# cpu.net
KiCad netlist of a schematic drawn in Altium Designer
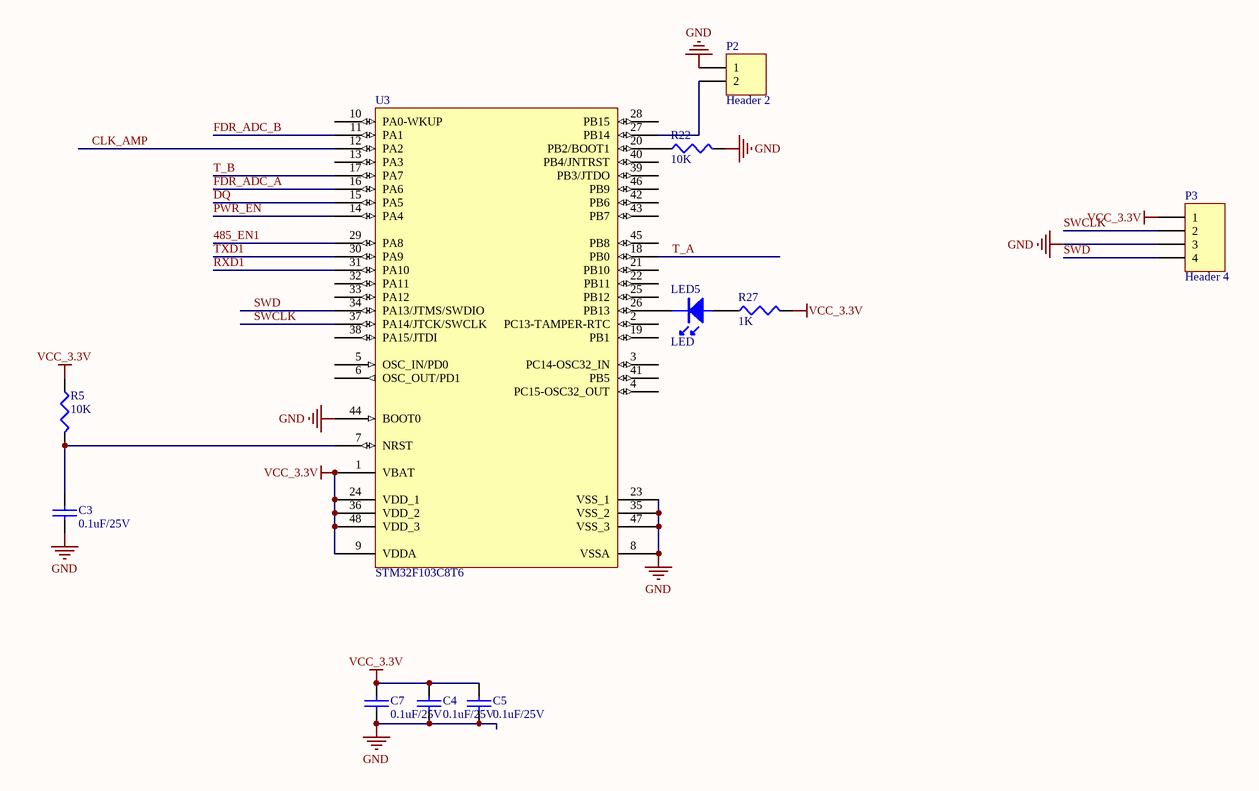
[diagram p0: cpu.SchDoc]

(export (version "E")
  (design (tool "Eeschema 10.0.6"))
  (components
    (comp (ref "C3")
      (value "0.1uF/25V")
      (footprint "0603C")
      (description "Capacitor")
      (libsource (lib "SM") (part "CAP"))
    )
    (comp (ref "C4")
      (value "0.1uF/25V")
      (footprint "0603C")
      (description "Capacitor")
      (libsource (lib "SM") (part "CAP"))
    )
    (comp (ref "C5")
      (value "0.1uF/25V")
      (footprint "0603C")
      (description "Capacitor")
      (libsource (lib "SM") (part "CAP"))
    )
    (comp (ref "C7")
      (value "0.1uF/25V")
      (footprint "0603C")
      (description "Capacitor")
      (libsource (lib "SM") (part "CAP"))
    )
    (comp (ref "LED5") (value "LED") (footprint "0603LED") (libsource (lib "我的元件库") (part "LED")))
    (comp (ref "P2")
      (value "Header 2")
      (footprint "HDR1X2")
      (description "Header, 2-Pin")
      (fields (field (name "PUBLISHER") "Altium Limited"))
      (libsource (lib "Miscellaneous Connectors") (part "Header 2"))
    )
    (comp (ref "P3")
      (value "Header 4")
      (footprint "HDR1X4")
      (description "Header, 4-Pin")
      (fields (field (name "PUBLISHER") "Altium Limited"))
      (libsource (lib "Miscellaneous Connectors") (part "Header 4"))
    )
    (comp (ref "R5")
      (value "10K")
      (footprint "0603R")
      (description "Resistor")
      (fields (field (name "PUBLISHER") "Altium Limited"))
      (libsource (lib "SM") (part "Res3"))
    )
    (comp (ref "R22")
      (value "10K")
      (footprint "0603R")
      (description "Resistor")
      (fields (field (name "PUBLISHER") "Altium Limited"))
      (libsource (lib "SM") (part "Res3"))
    )
    (comp (ref "R27")
      (value "1K")
      (footprint "0603R")
      (libsource (lib "ZWLIntegrated_Library") (part "RES1"))
    )
    (comp (ref "U3")
      (value "STM32F103C8T6")
      (footprint "TQFP-48")
      (description "STM32 ARM-based 32-bit MCU with 64 Kbytes Flash, 48-pin LQFP, Industrial Temperature")
      (fields (field (name "PUBLISHER") "Altium Limited"))
      (libsource (lib "ST Microcontroller 32-Bit STM32") (part "STM32F103C8T6"))
    )
  )
  (nets
    (net (code "1") (name "/485_EN1") (class "Default")
      (node (ref "U3") (pin "29") (pinfunction "PA8_29") (pintype "bidirectional"))
    )
    (net (code "2") (name "/CLK_AMP") (class "Default")
      (node (ref "U3") (pin "12") (pinfunction "PA2_12") (pintype "bidirectional"))
    )
    (net (code "3") (name "/DQ") (class "Default")
      (node (ref "U3") (pin "15") (pinfunction "PA5_15") (pintype "bidirectional"))
    )
    (net (code "4") (name "/FDR_ADC_A") (class "Default")
      (node (ref "U3") (pin "16") (pinfunction "PA6_16") (pintype "bidirectional"))
    )
    (net (code "5") (name "/FDR_ADC_B") (class "Default")
      (node (ref "U3") (pin "11") (pinfunction "PA1_11") (pintype "bidirectional"))
    )
    (net (code "6") (name "/PWR_EN") (class "Default")
      (node (ref "U3") (pin "14") (pinfunction "PA4_14") (pintype "bidirectional"))
    )
    (net (code "7") (name "/RXD1") (class "Default")
      (node (ref "U3") (pin "31") (pinfunction "PA10_31") (pintype "bidirectional"))
    )
    (net (code "8") (name "/SWCLK") (class "Default")
      (node (ref "P3") (pin "2") (pinfunction "2_2") (pintype "passive"))
      (node (ref "U3") (pin "37") (pinfunction "PA14/JTCK/SWCLK_37") (pintype "bidirectional"))
    )
    (net (code "9") (name "/SWD") (class "Default")
      (node (ref "P3") (pin "4") (pinfunction "4_4") (pintype "passive"))
      (node (ref "U3") (pin "34") (pinfunction "PA13/JTMS/SWDIO_34") (pintype "bidirectional"))
    )
    (net (code "10") (name "/TXD1") (class "Default")
      (node (ref "U3") (pin "30") (pinfunction "PA9_30") (pintype "bidirectional"))
    )
    (net (code "11") (name "/T_A") (class "Default")
      (node (ref "U3") (pin "18") (pinfunction "PB0_18") (pintype "bidirectional"))
    )
    (net (code "12") (name "/T_B") (class "Default")
      (node (ref "U3") (pin "17") (pinfunction "PA7_17") (pintype "bidirectional"))
    )
    (net (code "13") (name "GND") (class "Default")
      (node (ref "C3") (pin "1") (pinfunction "1_1") (pintype "passive"))
      (node (ref "C4") (pin "1") (pinfunction "1_1") (pintype "passive"))
      (node (ref "C5") (pin "1") (pinfunction "1_1") (pintype "passive"))
      (node (ref "C7") (pin "1") (pinfunction "1_1") (pintype "passive"))
      (node (ref "P2") (pin "1") (pinfunction "1_1") (pintype "passive"))
      (node (ref "P3") (pin "3") (pinfunction "3_3") (pintype "passive"))
      (node (ref "R22") (pin "2") (pinfunction "2_2") (pintype "passive"))
      (node (ref "U3") (pin "23") (pinfunction "VSS_1_23") (pintype "power_in"))
      (node (ref "U3") (pin "35") (pinfunction "VSS_2_35") (pintype "power_in"))
      (node (ref "U3") (pin "44") (pinfunction "BOOT0_44") (pintype "input"))
      (node (ref "U3") (pin "47") (pinfunction "VSS_3_47") (pintype "power_in"))
      (node (ref "U3") (pin "8") (pinfunction "VSSA_8") (pintype "power_in"))
    )
    (net (code "14") (name "Net-(LED5-Pad1)") (class "Default")
      (node (ref "LED5") (pin "1") (pinfunction "1_1") (pintype "passive"))
      (node (ref "R27") (pin "1") (pinfunction "1_1") (pintype "passive"))
    )
    (net (code "15") (name "Net-(U3-NRST)") (class "Default")
      (node (ref "C3") (pin "2") (pinfunction "2_2") (pintype "passive"))
      (node (ref "R5") (pin "2") (pinfunction "2_2") (pintype "passive"))
      (node (ref "U3") (pin "7") (pinfunction "NRST_7") (pintype "bidirectional"))
    )
    (net (code "16") (name "Net-(U3-PB2{slash}BOOT1)") (class "Default")
      (node (ref "R22") (pin "1") (pinfunction "1_1") (pintype "passive"))
      (node (ref "U3") (pin "20") (pinfunction "PB2/BOOT1_20") (pintype "bidirectional"))
    )
    (net (code "17") (name "Net-(U3-PB13)") (class "Default")
      (node (ref "LED5") (pin "2") (pinfunction "2_2") (pintype "passive"))
      (node (ref "U3") (pin "26") (pinfunction "PB13_26") (pintype "bidirectional"))
    )
    (net (code "18") (name "Net-(U3-PB14)") (class "Default")
      (node (ref "P2") (pin "2") (pinfunction "2_2") (pintype "passive"))
      (node (ref "U3") (pin "27") (pinfunction "PB14_27") (pintype "bidirectional"))
    )
    (net (code "19") (name "VCC_3.3V") (class "Default")
      (node (ref "C4") (pin "2") (pinfunction "2_2") (pintype "passive"))
      (node (ref "C5") (pin "2") (pinfunction "2_2") (pintype "passive"))
      (node (ref "C7") (pin "2") (pinfunction "2_2") (pintype "passive"))
      (node (ref "P3") (pin "1") (pinfunction "1_1") (pintype "passive"))
      (node (ref "R27") (pin "2") (pinfunction "2_2") (pintype "passive"))
      (node (ref "R5") (pin "1") (pinfunction "1_1") (pintype "passive"))
      (node (ref "U3") (pin "1") (pinfunction "VBAT_1") (pintype "power_in"))
      (node (ref "U3") (pin "24") (pinfunction "VDD_1_24") (pintype "power_in"))
      (node (ref "U3") (pin "36") (pinfunction "VDD_2_36") (pintype "power_in"))
      (node (ref "U3") (pin "48") (pinfunction "VDD_3_48") (pintype "power_in"))
      (node (ref "U3") (pin "9") (pinfunction "VDDA_9") (pintype "power_in"))
    )
    (net (code "20") (name "unconnected-(U3-OSC_IN{slash}PD0-Pad5)") (class "Default")
      (node (ref "U3") (pin "5") (pinfunction "OSC_IN/PD0_5") (pintype "input"))
    )
    (net (code "21") (name "unconnected-(U3-OSC_OUT{slash}PD1-Pad6)") (class "Default")
      (node (ref "U3") (pin "6") (pinfunction "OSC_OUT/PD1_6") (pintype "output"))
    )
    (net (code "22") (name "unconnected-(U3-PA0-WKUP-Pad10)") (class "Default")
      (node (ref "U3") (pin "10") (pinfunction "PA0-WKUP_10") (pintype "bidirectional"))
    )
    (net (code "23") (name "unconnected-(U3-PA3-Pad13)") (class "Default")
      (node (ref "U3") (pin "13") (pinfunction "PA3_13") (pintype "bidirectional"))
    )
    (net (code "24") (name "unconnected-(U3-PA11-Pad32)") (class "Default")
      (node (ref "U3") (pin "32") (pinfunction "PA11_32") (pintype "bidirectional"))
    )
    (net (code "25") (name "unconnected-(U3-PA12-Pad33)") (class "Default")
      (node (ref "U3") (pin "33") (pinfunction "PA12_33") (pintype "bidirectional"))
    )
    (net (code "26") (name "unconnected-(U3-PA15{slash}JTDI-Pad38)") (class "Default")
      (node (ref "U3") (pin "38") (pinfunction "PA15/JTDI_38") (pintype "bidirectional"))
    )
    (net (code "27") (name "unconnected-(U3-PB1-Pad19)") (class "Default")
      (node (ref "U3") (pin "19") (pinfunction "PB1_19") (pintype "bidirectional"))
    )
    (net (code "28") (name "unconnected-(U3-PB3{slash}JTDO-Pad39)") (class "Default")
      (node (ref "U3") (pin "39") (pinfunction "PB3/JTDO_39") (pintype "bidirectional"))
    )
    (net (code "29") (name "unconnected-(U3-PB4{slash}JNTRST-Pad40)") (class "Default")
      (node (ref "U3") (pin "40") (pinfunction "PB4/JNTRST_40") (pintype "bidirectional"))
    )
    (net (code "30") (name "unconnected-(U3-PB5-Pad41)") (class "Default")
      (node (ref "U3") (pin "41") (pinfunction "PB5_41") (pintype "bidirectional"))
    )
    (net (code "31") (name "unconnected-(U3-PB6-Pad42)") (class "Default")
      (node (ref "U3") (pin "42") (pinfunction "PB6_42") (pintype "bidirectional"))
    )
    (net (code "32") (name "unconnected-(U3-PB7-Pad43)") (class "Default")
      (node (ref "U3") (pin "43") (pinfunction "PB7_43") (pintype "bidirectional"))
    )
    (net (code "33") (name "unconnected-(U3-PB8-Pad45)") (class "Default")
      (node (ref "U3") (pin "45") (pinfunction "PB8_45") (pintype "bidirectional"))
    )
    (net (code "34") (name "unconnected-(U3-PB9-Pad46)") (class "Default")
      (node (ref "U3") (pin "46") (pinfunction "PB9_46") (pintype "bidirectional"))
    )
    (net (code "35") (name "unconnected-(U3-PB10-Pad21)") (class "Default")
      (node (ref "U3") (pin "21") (pinfunction "PB10_21") (pintype "bidirectional"))
    )
    (net (code "36") (name "unconnected-(U3-PB11-Pad22)") (class "Default")
      (node (ref "U3") (pin "22") (pinfunction "PB11_22") (pintype "bidirectional"))
    )
    (net (code "37") (name "unconnected-(U3-PB12-Pad25)") (class "Default")
      (node (ref "U3") (pin "25") (pinfunction "PB12_25") (pintype "bidirectional"))
    )
    (net (code "38") (name "unconnected-(U3-PB15-Pad28)") (class "Default")
      (node (ref "U3") (pin "28") (pinfunction "PB15_28") (pintype "bidirectional"))
    )
    (net (code "39") (name "unconnected-(U3-PC13-TAMPER-RTC-Pad2)") (class "Default")
      (node (ref "U3") (pin "2") (pinfunction "PC13-TAMPER-RTC_2") (pintype "bidirectional"))
    )
    (net (code "40") (name "unconnected-(U3-PC14-OSC32_IN-Pad3)") (class "Default")
      (node (ref "U3") (pin "3") (pinfunction "PC14-OSC32_IN_3") (pintype "bidirectional"))
    )
    (net (code "41") (name "unconnected-(U3-PC15-OSC32_OUT-Pad4)") (class "Default")
      (node (ref "U3") (pin "4") (pinfunction "PC15-OSC32_OUT_4") (pintype "bidirectional"))
    )
  )
)
